# DAC_Interface.net
KiCad netlist of a schematic drawn in Altium Designer
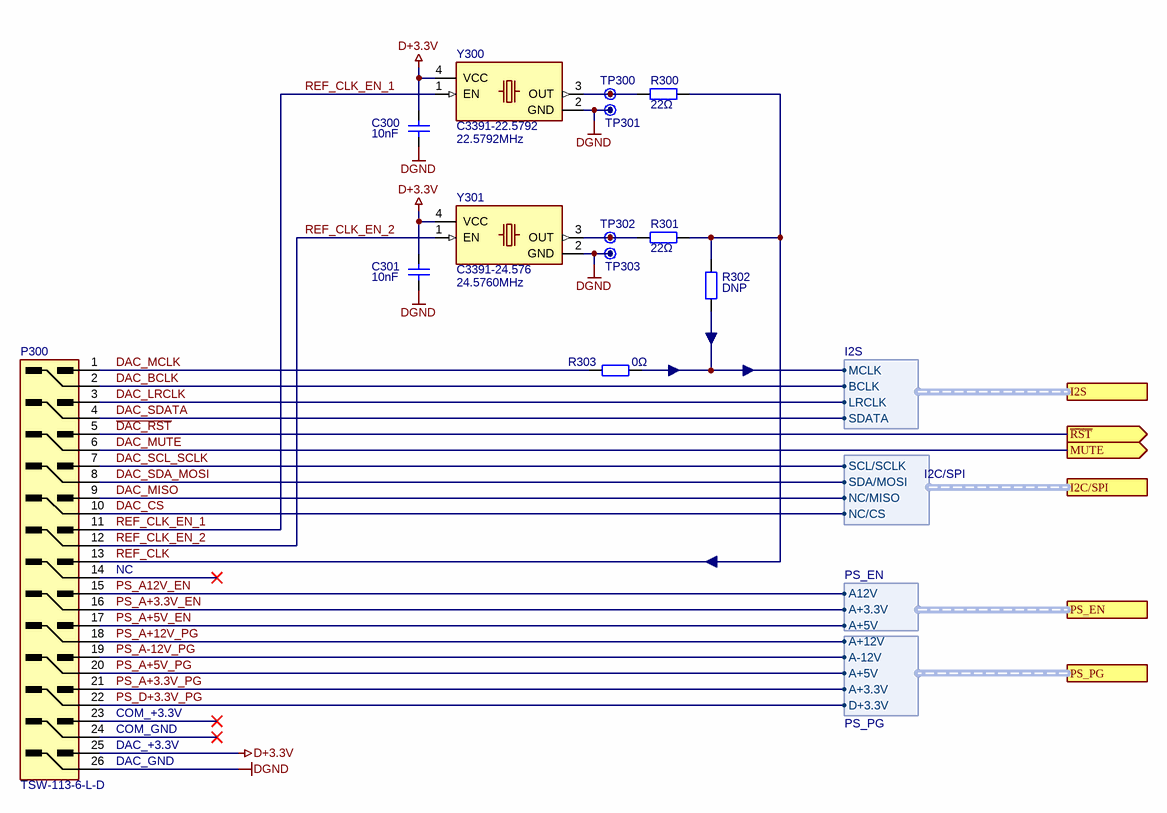
[diagram p0: DAC_Interface.SchDoc]

(export (version "E")
  (design (tool "Eeschema 10.0.6"))
  (components
    (comp (ref "C300")
      (value "10nF")
      (footprint "SMD0603CAP")
      (description "Ceramic Capacitor")
      (libsource (lib "Audio-Streamer") (part "Capacitor Ceramic"))
    )
    (comp (ref "C301")
      (value "10nF")
      (footprint "SMD0603CAP")
      (description "Ceramic Capacitor")
      (libsource (lib "Audio-Streamer") (part "Capacitor Ceramic"))
    )
    (comp (ref "P300")
      (value "TSW-113-6-L-D")
      (footprint "HEADER_2x13P_VERTICAL")
      (description "Header 13x2P")
      (libsource (lib "Audio-Streamer") (part "Header 13x2P"))
    )
    (comp (ref "R300")
      (value "22Ω")
      (footprint "SMD0603RES")
      (description "Resistor")
      (libsource (lib "Audio-Streamer") (part "Resistor"))
    )
    (comp (ref "R301")
      (value "22Ω")
      (footprint "SMD0603RES")
      (description "Resistor")
      (libsource (lib "Audio-Streamer") (part "Resistor"))
    )
    (comp (ref "R302")
      (value "DNP")
      (footprint "SMD0603RES")
      (description "Resistor")
      (libsource (lib "") (part "Resistor_1"))
    )
    (comp (ref "R303")
      (value "0Ω")
      (footprint "SMD0603RES")
      (description "Resistor")
      (libsource (lib "") (part "Resistor_2"))
    )
    (comp (ref "TP300")
      (value "Testpoint")
      (footprint "TP")
      (libsource (lib "Audio-Streamer") (part "Testpoint"))
    )
    (comp (ref "TP301")
      (value "Testpoint")
      (footprint "TP")
      (libsource (lib "Audio-Streamer") (part "Testpoint"))
    )
    (comp (ref "TP302")
      (value "Testpoint")
      (footprint "TP")
      (libsource (lib "Audio-Streamer") (part "Testpoint"))
    )
    (comp (ref "TP303")
      (value "Testpoint")
      (footprint "TP")
      (libsource (lib "Audio-Streamer") (part "Testpoint"))
    )
    (comp (ref "Y300")
      (value "C3391-22.5792")
      (footprint "OSC_CRYSTEK")
      (description "HCMOS Oscillator")
      (fields (field (name "FREQUENCY") "22.5792MHz"))
      (libsource (lib "Audio-Streamer") (part "Oscillator Crystek"))
    )
    (comp (ref "Y301")
      (value "C3391-24.576")
      (footprint "OSC_CRYSTEK")
      (description "HCMOS Oscillator")
      (fields (field (name "FREQUENCY") "24.5760MHz"))
      (libsource (lib "Audio-Streamer") (part "Oscillator Crystek"))
    )
  )
  (nets
    (net (code "5") (name "/DAC_BCLK") (class "Default")
      (node (ref "P300") (pin "2") (pinfunction "2_2") (pintype "passive"))
    )
    (net (code "6") (name "/DAC_CS") (class "Default")
      (node (ref "P300") (pin "10") (pinfunction "10_10") (pintype "passive"))
    )
    (net (code "7") (name "/DAC_LRCLK") (class "Default")
      (node (ref "P300") (pin "3") (pinfunction "3_3") (pintype "passive"))
    )
    (net (code "8") (name "/DAC_MCLK") (class "Default")
      (node (ref "P300") (pin "1") (pinfunction "1_1") (pintype "passive"))
      (node (ref "R303") (pin "2") (pinfunction "2_2") (pintype "passive"))
    )
    (net (code "9") (name "/DAC_MISO") (class "Default")
      (node (ref "P300") (pin "9") (pinfunction "9_9") (pintype "passive"))
    )
    (net (code "10") (name "/DAC_MUTE") (class "Default")
      (node (ref "P300") (pin "6") (pinfunction "6_6") (pintype "passive"))
    )
    (net (code "11") (name "/DAC_SCL_SCLK") (class "Default")
      (node (ref "P300") (pin "7") (pinfunction "7_7") (pintype "passive"))
    )
    (net (code "12") (name "/DAC_SDATA") (class "Default")
      (node (ref "P300") (pin "4") (pinfunction "4_4") (pintype "passive"))
    )
    (net (code "13") (name "/DAC_SDA_MOSI") (class "Default")
      (node (ref "P300") (pin "8") (pinfunction "8_8") (pintype "passive"))
    )
    (net (code "14") (name "/PS_A+3.3V_EN") (class "Default")
      (node (ref "P300") (pin "16") (pinfunction "16_16") (pintype "passive"))
    )
    (net (code "15") (name "/PS_A+3.3V_PG") (class "Default")
      (node (ref "P300") (pin "21") (pinfunction "21_21") (pintype "passive"))
    )
    (net (code "16") (name "/PS_A+5V_EN") (class "Default")
      (node (ref "P300") (pin "17") (pinfunction "17_17") (pintype "passive"))
    )
    (net (code "17") (name "/PS_A+5V_PG") (class "Default")
      (node (ref "P300") (pin "20") (pinfunction "20_20") (pintype "passive"))
    )
    (net (code "18") (name "/PS_A+12V_PG") (class "Default")
      (node (ref "P300") (pin "18") (pinfunction "18_18") (pintype "passive"))
    )
    (net (code "19") (name "/PS_A-12V_PG") (class "Default")
      (node (ref "P300") (pin "19") (pinfunction "19_19") (pintype "passive"))
    )
    (net (code "20") (name "/PS_A12V_EN") (class "Default")
      (node (ref "P300") (pin "15") (pinfunction "15_15") (pintype "passive"))
    )
    (net (code "21") (name "/PS_D+3.3V_PG") (class "Default")
      (node (ref "P300") (pin "22") (pinfunction "22_22") (pintype "passive"))
    )
    (net (code "22") (name "/REF_CLK") (class "Default")
      (node (ref "P300") (pin "13") (pinfunction "13_13") (pintype "passive"))
      (node (ref "R300") (pin "2") (pinfunction "2_2") (pintype "passive"))
      (node (ref "R301") (pin "2") (pinfunction "2_2") (pintype "passive"))
      (node (ref "R302") (pin "1") (pinfunction "1_1") (pintype "passive"))
    )
    (net (code "23") (name "/REF_CLK_EN_1") (class "Default")
      (node (ref "P300") (pin "11") (pinfunction "11_11") (pintype "passive"))
      (node (ref "Y300") (pin "1") (pinfunction "EN_1") (pintype "input"))
    )
    (net (code "24") (name "/REF_CLK_EN_2") (class "Default")
      (node (ref "P300") (pin "12") (pinfunction "12_12") (pintype "passive"))
      (node (ref "Y301") (pin "1") (pinfunction "EN_1") (pintype "input"))
    )
    (net (code "29") (name "/~{DAC_RST}") (class "Default")
      (node (ref "P300") (pin "5") (pinfunction "5_5") (pintype "passive"))
    )
    (net (code "30") (name "D+3.3V") (class "Default")
      (node (ref "C300") (pin "1") (pinfunction "1_1") (pintype "passive"))
      (node (ref "C301") (pin "1") (pinfunction "1_1") (pintype "passive"))
      (node (ref "P300") (pin "25") (pinfunction "25_25") (pintype "passive"))
      (node (ref "Y300") (pin "4") (pinfunction "VCC_4") (pintype "power_in"))
      (node (ref "Y301") (pin "4") (pinfunction "VCC_4") (pintype "power_in"))
    )
    (net (code "31") (name "DGND") (class "Default")
      (node (ref "C300") (pin "2") (pinfunction "q_2") (pintype "passive"))
      (node (ref "C301") (pin "2") (pinfunction "q_2") (pintype "passive"))
      (node (ref "P300") (pin "26") (pinfunction "26_26") (pintype "passive"))
      (node (ref "TP301") (pin "1") (pinfunction "1_1") (pintype "passive"))
      (node (ref "TP303") (pin "1") (pinfunction "1_1") (pintype "passive"))
      (node (ref "Y300") (pin "2") (pinfunction "GND_2") (pintype "power_in"))
      (node (ref "Y301") (pin "2") (pinfunction "GND_2") (pintype "power_in"))
    )
    (net (code "32") (name "Net-(R302-Pad2)") (class "Default")
      (node (ref "R302") (pin "2") (pinfunction "2_2") (pintype "passive"))
      (node (ref "R303") (pin "1") (pinfunction "1_1") (pintype "passive"))
    )
    (net (code "33") (name "Net-(Y300-OUT)") (class "Default")
      (node (ref "R300") (pin "1") (pinfunction "1_1") (pintype "passive"))
      (node (ref "TP300") (pin "1") (pinfunction "1_1") (pintype "passive"))
      (node (ref "Y300") (pin "3") (pinfunction "OUT_3") (pintype "output"))
    )
    (net (code "34") (name "Net-(Y301-OUT)") (class "Default")
      (node (ref "R301") (pin "1") (pinfunction "1_1") (pintype "passive"))
      (node (ref "TP302") (pin "1") (pinfunction "1_1") (pintype "passive"))
      (node (ref "Y301") (pin "3") (pinfunction "OUT_3") (pintype "output"))
    )
    (net (code "35") (name "unconnected-(P300-Pad14)") (class "Default")
      (node (ref "P300") (pin "14") (pinfunction "14_14") (pintype "passive+no_connect"))
    )
    (net (code "36") (name "unconnected-(P300-Pad23)") (class "Default")
      (node (ref "P300") (pin "23") (pinfunction "23_23") (pintype "passive+no_connect"))
    )
    (net (code "37") (name "unconnected-(P300-Pad24)") (class "Default")
      (node (ref "P300") (pin "24") (pinfunction "24_24") (pintype "passive+no_connect"))
    )
  )
)
